# Sheet2.net
KiCad netlist of a schematic drawn in Altium Designer
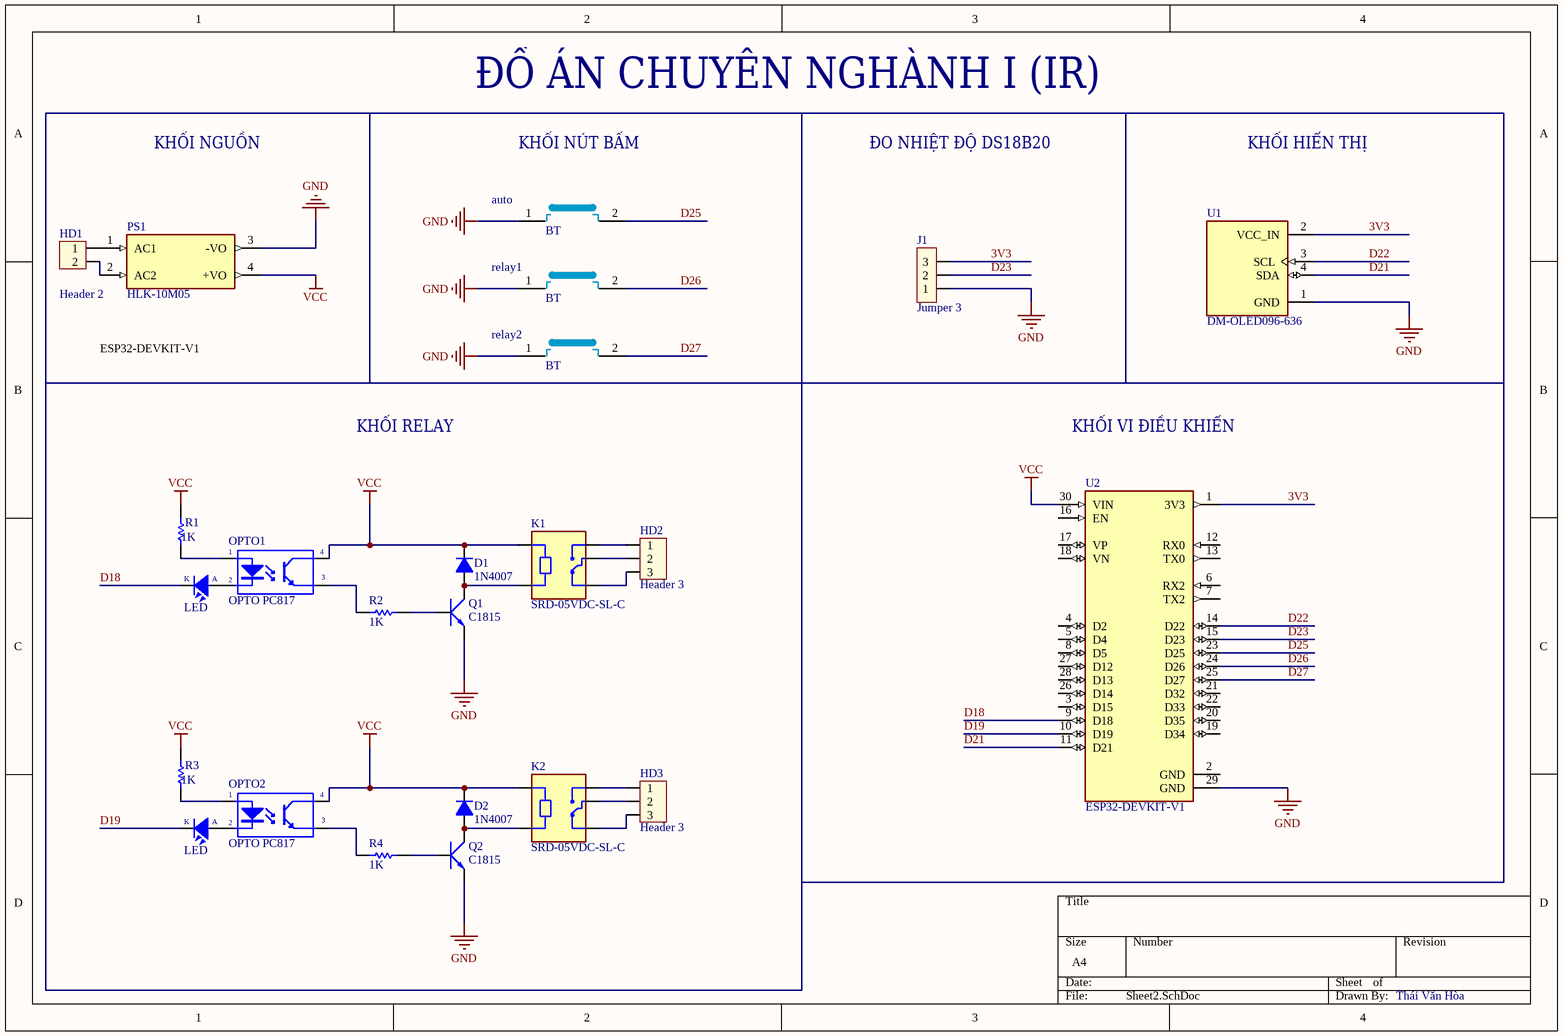
[diagram p0: Sheet2.SchDoc]

(export (version "E")
  (design (tool "Eeschema 10.0.6"))
  (components
    (comp (ref "BT1") (value "BT") (footprint "SW4") (libsource (lib "My library altium") (part "BUTTON")))
    (comp (ref "BT2") (value "BT") (footprint "SW4") (libsource (lib "My library altium") (part "BUTTON")))
    (comp (ref "BT3") (value "BT") (footprint "SW4") (libsource (lib "My library altium") (part "BUTTON")))
    (comp (ref "D1")
      (value "1N4007")
      (footprint "D1A")
      (description "Diode 1A")
      (libsource (lib "syhaunguyen") (part "D1A"))
    )
    (comp (ref "D2")
      (value "1N4007")
      (footprint "D1A")
      (description "Diode 1A")
      (libsource (lib "syhaunguyen") (part "D1A"))
    )
    (comp (ref "HD1")
      (value "Header 2")
      (footprint "HED2")
      (description "Header 2 (Green)")
      (libsource (lib "syhaunguyen") (part "Hed2"))
    )
    (comp (ref "HD2")
      (value "Header 3")
      (footprint "HED3")
      (description "Header 3 (Green)")
      (libsource (lib "My library altium") (part "Header 3"))
    )
    (comp (ref "HD3")
      (value "Header 3")
      (footprint "HED3")
      (description "Header 3 (Green)")
      (libsource (lib "My library altium") (part "Header 3"))
    )
    (comp (ref "J1") (value "Jumper 3") (footprint "JP3") (libsource (lib "syhaunguyen") (part "JP3")))
    (comp (ref "K1")
      (value "SRD-05VDC-SL-C")
      (footprint "RELAY_SRD-05VDC-SL-C")
      (fields (field (name "MF") "Songle Relay"))
      (libsource (lib "SRD-05VDC-SL-C") (part "SRD-05VDC-SL-C"))
    )
    (comp (ref "K2")
      (value "SRD-05VDC-SL-C")
      (footprint "RELAY_SRD-05VDC-SL-C")
      (fields (field (name "MF") "Songle Relay"))
      (libsource (lib "SRD-05VDC-SL-C") (part "SRD-05VDC-SL-C"))
    )
    (comp (ref "LED1")
      (value "LED")
      (footprint "LED-3")
      (description "LED Single colour Green and Red")
      (libsource (lib "My library altium") (part "LED"))
    )
    (comp (ref "LED2")
      (value "LED")
      (footprint "LED-3")
      (description "LED Single colour Green and Red")
      (libsource (lib "My library altium") (part "LED"))
    )
    (comp (ref "OPTO1")
      (value "OPTO PC817")
      (footprint "DIP4/W0.3")
      (description "Single Opto")
      (libsource (lib "My library altium") (part "OPTO PC817"))
    )
    (comp (ref "OPTO2")
      (value "OPTO PC817")
      (footprint "DIP4/W0.3")
      (description "Single Opto")
      (libsource (lib "My library altium") (part "OPTO PC817"))
    )
    (comp (ref "PS1")
      (value "HLK-10M05")
      (footprint "CONV_HLK-10M05")
      (description "10W Ultra-Compact Power Module")
      (fields (field (name "MF") "Hi-link"))
      (libsource (lib "HLK-10M05") (part "HLK-10M05"))
    )
    (comp (ref "Q1")
      (value "C1815")
      (footprint "QTO-92")
      (description "NPN 600mW, ECB")
      (libsource (lib "syhaunguyen") (part "C1815"))
    )
    (comp (ref "Q2")
      (value "C1815")
      (footprint "QTO-92")
      (description "NPN 600mW, ECB")
      (libsource (lib "syhaunguyen") (part "C1815"))
    )
    (comp (ref "R1")
      (value "1K")
      (footprint "R1/4W")
      (description "Resistor")
      (fields
        (field (name "MANUFACTURER") "Generic Components")
        (field (name "Comment") "Res1")
        (field (name "PUBLISHER") "Altium Hobart Technology Centre")
      )
      (libsource (lib "syhaunguyen") (part "Res1_4"))
    )
    (comp (ref "R2")
      (value "1K")
      (footprint "R1/4W")
      (description "Resistor")
      (fields
        (field (name "MANUFACTURER") "Generic Components")
        (field (name "Comment") "Res1")
        (field (name "PUBLISHER") "Altium Hobart Technology Centre")
      )
      (libsource (lib "syhaunguyen") (part "Res1_4"))
    )
    (comp (ref "R3")
      (value "1K")
      (footprint "R1/4W")
      (description "Resistor")
      (fields
        (field (name "MANUFACTURER") "Generic Components")
        (field (name "Comment") "Res1")
        (field (name "PUBLISHER") "Altium Hobart Technology Centre")
      )
      (libsource (lib "syhaunguyen") (part "Res1_4"))
    )
    (comp (ref "R4")
      (value "1K")
      (footprint "R1/4W")
      (description "Resistor")
      (fields
        (field (name "MANUFACTURER") "Generic Components")
        (field (name "Comment") "Res1")
        (field (name "PUBLISHER") "Altium Hobart Technology Centre")
      )
      (libsource (lib "syhaunguyen") (part "Res1_4"))
    )
    (comp (ref "U1")
      (value "DM-OLED096-636")
      (footprint "MODULE_DM-OLED096-636")
      (description "0.96â€ 128 X 64 MONOCHROME GRAPHIC OLED DISPLAY MODULE - I2C")
      (fields (field (name "MF") "Display Module"))
      (libsource (lib "DM-OLED096-636") (part "DM-OLED096-636"))
    )
    (comp (ref "U2")
      (value "ESP32-DEVKIT-V1")
      (footprint "MODULE_ESP32_DEVKIT_V1")
      (fields (field (name "MF") "Do it"))
      (libsource (lib "ESP32-DEVKIT-V1") (part "ESP32-DEVKIT-V1"))
    )
  )
  (nets
    (net (code "1") (name "/3V3") (class "Default")
      (node (ref "J1") (pin "3") (pinfunction "3_3") (pintype "passive"))
      (node (ref "U1") (pin "2") (pinfunction "VCC_IN_2") (pintype "power_in"))
      (node (ref "U2") (pin "1") (pinfunction "3V3_1") (pintype "output"))
    )
    (net (code "2") (name "/D18") (class "Default")
      (node (ref "LED1") (pin "2") (pinfunction "K_2") (pintype "passive"))
      (node (ref "U2") (pin "9") (pinfunction "D18_9") (pintype "bidirectional"))
    )
    (net (code "3") (name "/D19") (class "Default")
      (node (ref "LED2") (pin "2") (pinfunction "K_2") (pintype "passive"))
      (node (ref "U2") (pin "10") (pinfunction "D19_10") (pintype "bidirectional"))
    )
    (net (code "4") (name "/D21") (class "Default")
      (node (ref "U1") (pin "4") (pinfunction "SDA_4") (pintype "bidirectional"))
      (node (ref "U2") (pin "11") (pinfunction "D21_11") (pintype "bidirectional"))
    )
    (net (code "5") (name "/D22") (class "Default")
      (node (ref "U1") (pin "3") (pinfunction "SCL_3") (pintype "input"))
      (node (ref "U2") (pin "14") (pinfunction "D22_14") (pintype "bidirectional"))
    )
    (net (code "6") (name "/D23") (class "Default")
      (node (ref "J1") (pin "2") (pinfunction "2_2") (pintype "passive"))
      (node (ref "U2") (pin "15") (pinfunction "D23_15") (pintype "bidirectional"))
    )
    (net (code "7") (name "/D25") (class "Default")
      (node (ref "BT1") (pin "2") (pinfunction "2_2") (pintype "passive"))
      (node (ref "U2") (pin "23") (pinfunction "D25_23") (pintype "bidirectional"))
    )
    (net (code "8") (name "/D26") (class "Default")
      (node (ref "BT2") (pin "2") (pinfunction "2_2") (pintype "passive"))
      (node (ref "U2") (pin "24") (pinfunction "D26_24") (pintype "bidirectional"))
    )
    (net (code "9") (name "/D27") (class "Default")
      (node (ref "BT3") (pin "2") (pinfunction "2_2") (pintype "passive"))
      (node (ref "U2") (pin "25") (pinfunction "D27_25") (pintype "bidirectional"))
    )
    (net (code "10") (name "GND") (class "Default")
      (node (ref "BT1") (pin "1") (pinfunction "1_1") (pintype "passive"))
      (node (ref "BT2") (pin "1") (pinfunction "1_1") (pintype "passive"))
      (node (ref "BT3") (pin "1") (pinfunction "1_1") (pintype "passive"))
      (node (ref "J1") (pin "1") (pinfunction "1_1") (pintype "passive"))
      (node (ref "PS1") (pin "3") (pinfunction "-VO_3") (pintype "output"))
      (node (ref "Q1") (pin "1") (pinfunction "E_1") (pintype "passive"))
      (node (ref "Q2") (pin "1") (pinfunction "E_1") (pintype "passive"))
      (node (ref "U1") (pin "1") (pinfunction "GND_1") (pintype "power_in"))
      (node (ref "U2") (pin "29") (pinfunction "GND_29") (pintype "power_in"))
    )
    (net (code "11") (name "Net-(D1-A)") (class "Default")
      (node (ref "D1") (pin "1") (pinfunction "A_1") (pintype "passive"))
      (node (ref "K1") (pin "A2") (pinfunction "A2_A2") (pintype "passive"))
      (node (ref "Q1") (pin "2") (pinfunction "C_2") (pintype "passive"))
    )
    (net (code "12") (name "Net-(D2-A)") (class "Default")
      (node (ref "D2") (pin "1") (pinfunction "A_1") (pintype "passive"))
      (node (ref "K2") (pin "A2") (pinfunction "A2_A2") (pintype "passive"))
      (node (ref "Q2") (pin "2") (pinfunction "C_2") (pintype "passive"))
    )
    (net (code "13") (name "Net-(HD2-Pad1)") (class "Default")
      (node (ref "HD2") (pin "1") (pinfunction "1_1") (pintype "passive"))
      (node (ref "K1") (pin "NO") (pinfunction "NO_NO") (pintype "passive"))
    )
    (net (code "14") (name "Net-(HD2-Pad2)") (class "Default")
      (node (ref "HD2") (pin "2") (pinfunction "2_2") (pintype "passive"))
      (node (ref "K1") (pin "COM") (pinfunction "COM_COM") (pintype "passive"))
    )
    (net (code "15") (name "Net-(HD2-Pad3)") (class "Default")
      (node (ref "HD2") (pin "3") (pinfunction "3_3") (pintype "passive"))
      (node (ref "K1") (pin "NC") (pinfunction "NC_NC") (pintype "passive"))
    )
    (net (code "16") (name "Net-(HD3-Pad1)") (class "Default")
      (node (ref "HD3") (pin "1") (pinfunction "1_1") (pintype "passive"))
      (node (ref "K2") (pin "NO") (pinfunction "NO_NO") (pintype "passive"))
    )
    (net (code "17") (name "Net-(HD3-Pad2)") (class "Default")
      (node (ref "HD3") (pin "2") (pinfunction "2_2") (pintype "passive"))
      (node (ref "K2") (pin "COM") (pinfunction "COM_COM") (pintype "passive"))
    )
    (net (code "18") (name "Net-(HD3-Pad3)") (class "Default")
      (node (ref "HD3") (pin "3") (pinfunction "3_3") (pintype "passive"))
      (node (ref "K2") (pin "NC") (pinfunction "NC_NC") (pintype "passive"))
    )
    (net (code "19") (name "Net-(LED1-A)") (class "Default")
      (node (ref "LED1") (pin "1") (pinfunction "A_1") (pintype "passive"))
      (node (ref "OPTO1") (pin "2") (pinfunction "K_2") (pintype "passive"))
    )
    (net (code "20") (name "Net-(LED2-A)") (class "Default")
      (node (ref "LED2") (pin "1") (pinfunction "A_1") (pintype "passive"))
      (node (ref "OPTO2") (pin "2") (pinfunction "K_2") (pintype "passive"))
    )
    (net (code "21") (name "Net-(OPTO1-A)") (class "Default")
      (node (ref "OPTO1") (pin "1") (pinfunction "A_1") (pintype "passive"))
      (node (ref "R1") (pin "1") (pinfunction "1_1") (pintype "passive"))
    )
    (net (code "22") (name "Net-(OPTO1-E)") (class "Default")
      (node (ref "OPTO1") (pin "3") (pinfunction "E_3") (pintype "passive"))
      (node (ref "R2") (pin "2") (pinfunction "2_2") (pintype "passive"))
    )
    (net (code "23") (name "Net-(OPTO2-A)") (class "Default")
      (node (ref "OPTO2") (pin "1") (pinfunction "A_1") (pintype "passive"))
      (node (ref "R3") (pin "1") (pinfunction "1_1") (pintype "passive"))
    )
    (net (code "24") (name "Net-(OPTO2-E)") (class "Default")
      (node (ref "OPTO2") (pin "3") (pinfunction "E_3") (pintype "passive"))
      (node (ref "R4") (pin "2") (pinfunction "2_2") (pintype "passive"))
    )
    (net (code "25") (name "Net-(PS1-AC1)") (class "Default")
      (node (ref "HD1") (pin "1") (pinfunction "1_1") (pintype "passive"))
      (node (ref "PS1") (pin "1") (pinfunction "AC1_1") (pintype "input"))
    )
    (net (code "26") (name "Net-(PS1-AC2)") (class "Default")
      (node (ref "HD1") (pin "2") (pinfunction "2_2") (pintype "passive"))
      (node (ref "PS1") (pin "2") (pinfunction "AC2_2") (pintype "input"))
    )
    (net (code "27") (name "Net-(Q1-B)") (class "Default")
      (node (ref "Q1") (pin "3") (pinfunction "B_3") (pintype "passive"))
      (node (ref "R2") (pin "1") (pinfunction "1_1") (pintype "passive"))
    )
    (net (code "28") (name "Net-(Q2-B)") (class "Default")
      (node (ref "Q2") (pin "3") (pinfunction "B_3") (pintype "passive"))
      (node (ref "R4") (pin "1") (pinfunction "1_1") (pintype "passive"))
    )
    (net (code "29") (name "VCC") (class "Default")
      (node (ref "D1") (pin "2") (pinfunction "K_2") (pintype "passive"))
      (node (ref "D2") (pin "2") (pinfunction "K_2") (pintype "passive"))
      (node (ref "K1") (pin "A1") (pinfunction "A1_A1") (pintype "passive"))
      (node (ref "K2") (pin "A1") (pinfunction "A1_A1") (pintype "passive"))
      (node (ref "OPTO1") (pin "4") (pinfunction "C_4") (pintype "passive"))
      (node (ref "OPTO2") (pin "4") (pinfunction "C_4") (pintype "passive"))
      (node (ref "PS1") (pin "4") (pinfunction "+VO_4") (pintype "output"))
      (node (ref "R1") (pin "2") (pinfunction "2_2") (pintype "passive"))
      (node (ref "R3") (pin "2") (pinfunction "2_2") (pintype "passive"))
      (node (ref "U2") (pin "30") (pinfunction "VIN_30") (pintype "input"))
    )
    (net (code "30") (name "unconnected-(U2-D2-Pad4)") (class "Default")
      (node (ref "U2") (pin "4") (pinfunction "D2_4") (pintype "bidirectional"))
    )
    (net (code "31") (name "unconnected-(U2-D4-Pad5)") (class "Default")
      (node (ref "U2") (pin "5") (pinfunction "D4_5") (pintype "bidirectional"))
    )
    (net (code "32") (name "unconnected-(U2-D5-Pad8)") (class "Default")
      (node (ref "U2") (pin "8") (pinfunction "D5_8") (pintype "bidirectional"))
    )
    (net (code "33") (name "unconnected-(U2-D12-Pad27)") (class "Default")
      (node (ref "U2") (pin "27") (pinfunction "D12_27") (pintype "bidirectional"))
    )
    (net (code "34") (name "unconnected-(U2-D13-Pad28)") (class "Default")
      (node (ref "U2") (pin "28") (pinfunction "D13_28") (pintype "bidirectional"))
    )
    (net (code "35") (name "unconnected-(U2-D14-Pad26)") (class "Default")
      (node (ref "U2") (pin "26") (pinfunction "D14_26") (pintype "bidirectional"))
    )
    (net (code "36") (name "unconnected-(U2-D15-Pad3)") (class "Default")
      (node (ref "U2") (pin "3") (pinfunction "D15_3") (pintype "bidirectional"))
    )
    (net (code "37") (name "unconnected-(U2-D32-Pad21)") (class "Default")
      (node (ref "U2") (pin "21") (pinfunction "D32_21") (pintype "bidirectional"))
    )
    (net (code "38") (name "unconnected-(U2-D33-Pad22)") (class "Default")
      (node (ref "U2") (pin "22") (pinfunction "D33_22") (pintype "bidirectional"))
    )
    (net (code "39") (name "unconnected-(U2-D34-Pad19)") (class "Default")
      (node (ref "U2") (pin "19") (pinfunction "D34_19") (pintype "bidirectional"))
    )
    (net (code "40") (name "unconnected-(U2-D35-Pad20)") (class "Default")
      (node (ref "U2") (pin "20") (pinfunction "D35_20") (pintype "bidirectional"))
    )
    (net (code "41") (name "unconnected-(U2-EN-Pad16)") (class "Default")
      (node (ref "U2") (pin "16") (pinfunction "EN_16") (pintype "input"))
    )
    (net (code "42") (name "unconnected-(U2-GND-Pad2)") (class "Default")
      (node (ref "U2") (pin "2") (pinfunction "GND_2") (pintype "power_in"))
    )
    (net (code "43") (name "unconnected-(U2-RX0-Pad12)") (class "Default")
      (node (ref "U2") (pin "12") (pinfunction "RX0_12") (pintype "input"))
    )
    (net (code "44") (name "unconnected-(U2-RX2-Pad6)") (class "Default")
      (node (ref "U2") (pin "6") (pinfunction "RX2_6") (pintype "input"))
    )
    (net (code "45") (name "unconnected-(U2-TX0-Pad13)") (class "Default")
      (node (ref "U2") (pin "13") (pinfunction "TX0_13") (pintype "output"))
    )
    (net (code "46") (name "unconnected-(U2-TX2-Pad7)") (class "Default")
      (node (ref "U2") (pin "7") (pinfunction "TX2_7") (pintype "output"))
    )
    (net (code "47") (name "unconnected-(U2-VN-Pad18)") (class "Default")
      (node (ref "U2") (pin "18") (pinfunction "VN_18") (pintype "bidirectional"))
    )
    (net (code "48") (name "unconnected-(U2-VP-Pad17)") (class "Default")
      (node (ref "U2") (pin "17") (pinfunction "VP_17") (pintype "bidirectional"))
    )
  )
)
